# AFE1.net
KiCad netlist of a schematic drawn in Altium Designer
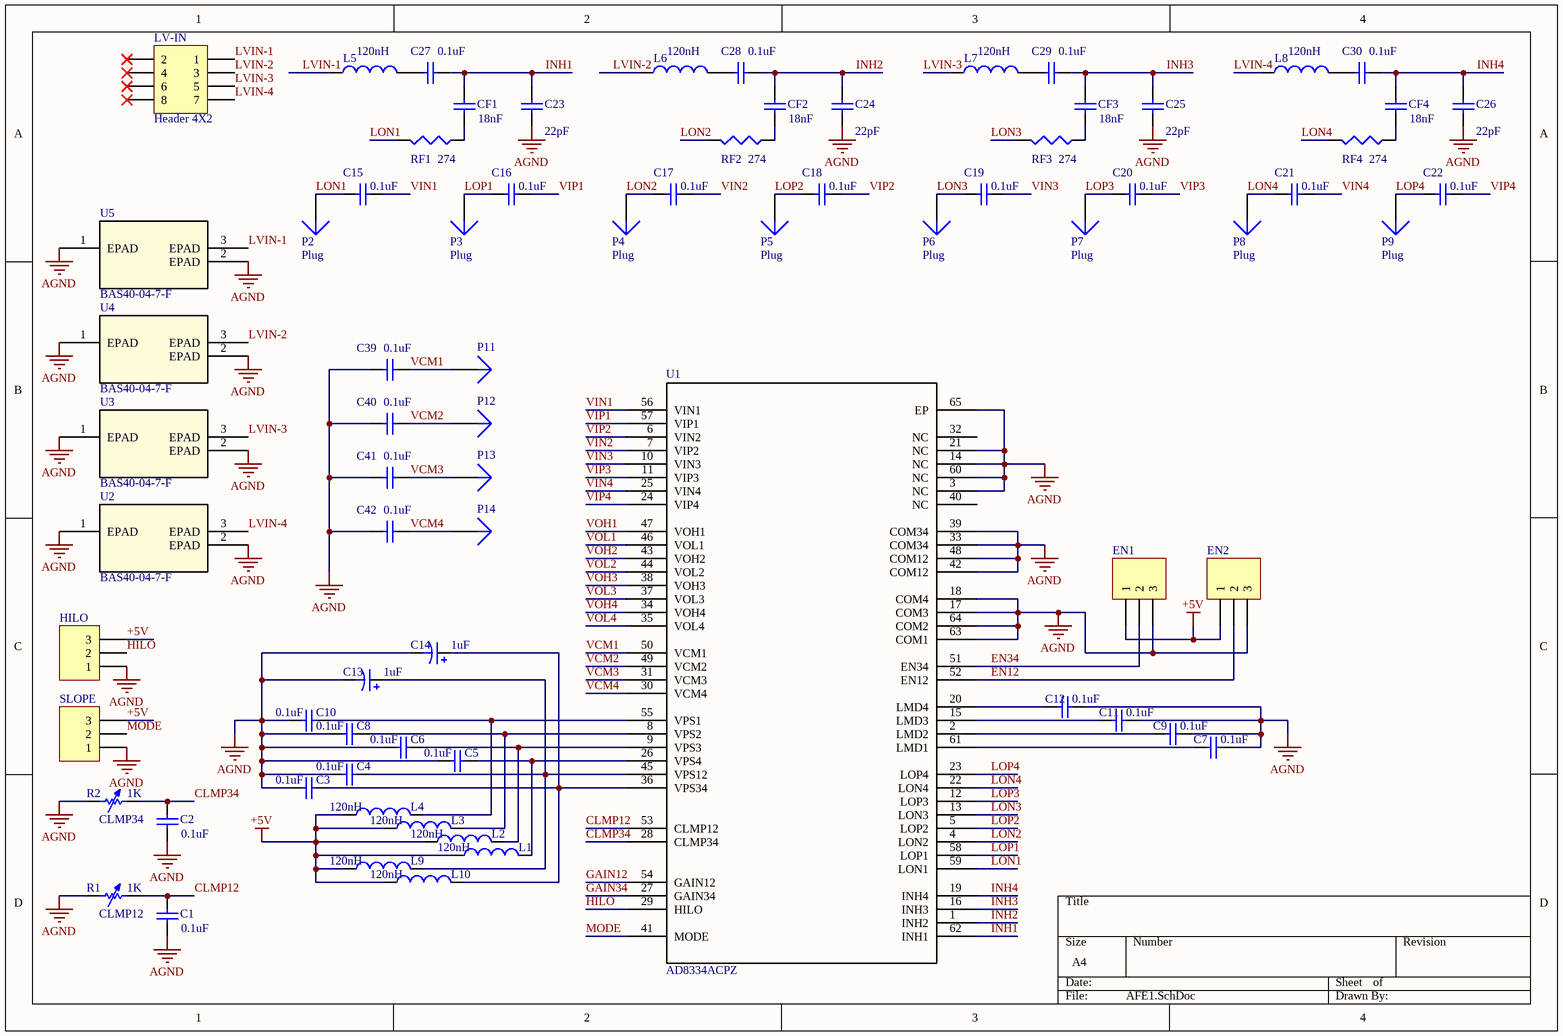
[diagram p0: AFE1.SchDoc]

(export (version "E")
  (design (tool "Eeschema 10.0.6"))
  (components
    (comp (ref "C1")
      (value "0.1uF")
      (footprint "1608[0603]")
      (description "Capacitor (Semiconductor SIM Model)")
      (fields (field (name "PUBLISHER") "Altium Limited"))
      (libsource (lib "Miscellaneous Devices") (part "Cap Semi"))
    )
    (comp (ref "C2")
      (value "0.1uF")
      (footprint "1608[0603]")
      (description "Capacitor (Semiconductor SIM Model)")
      (fields (field (name "PUBLISHER") "Altium Limited"))
      (libsource (lib "Miscellaneous Devices") (part "Cap Semi"))
    )
    (comp (ref "C3")
      (value "0.1uF")
      (footprint "1608[0603]")
      (description "Capacitor (Semiconductor SIM Model)")
      (fields (field (name "PUBLISHER") "Altium Limited"))
      (libsource (lib "Miscellaneous Devices") (part "Cap Semi"))
    )
    (comp (ref "C4")
      (value "0.1uF")
      (footprint "1608[0603]")
      (description "Capacitor (Semiconductor SIM Model)")
      (fields (field (name "PUBLISHER") "Altium Limited"))
      (libsource (lib "Miscellaneous Devices") (part "Cap Semi"))
    )
    (comp (ref "C5")
      (value "0.1uF")
      (footprint "1608[0603]")
      (description "Capacitor (Semiconductor SIM Model)")
      (fields (field (name "PUBLISHER") "Altium Limited"))
      (libsource (lib "Miscellaneous Devices") (part "Cap Semi"))
    )
    (comp (ref "C6")
      (value "0.1uF")
      (footprint "1608[0603]")
      (description "Capacitor (Semiconductor SIM Model)")
      (fields (field (name "PUBLISHER") "Altium Limited"))
      (libsource (lib "Miscellaneous Devices") (part "Cap Semi"))
    )
    (comp (ref "C7")
      (value "0.1uF")
      (footprint "1608[0603]")
      (description "Capacitor (Semiconductor SIM Model)")
      (fields (field (name "PUBLISHER") "Altium Limited"))
      (libsource (lib "Miscellaneous Devices") (part "Cap Semi"))
    )
    (comp (ref "C8")
      (value "0.1uF")
      (footprint "1608[0603]")
      (description "Capacitor (Semiconductor SIM Model)")
      (fields (field (name "PUBLISHER") "Altium Limited"))
      (libsource (lib "Miscellaneous Devices") (part "Cap Semi"))
    )
    (comp (ref "C9")
      (value "0.1uF")
      (footprint "1608[0603]")
      (description "Capacitor (Semiconductor SIM Model)")
      (fields (field (name "PUBLISHER") "Altium Limited"))
      (libsource (lib "Miscellaneous Devices") (part "Cap Semi"))
    )
    (comp (ref "C10")
      (value "0.1uF")
      (footprint "1608[0603]")
      (description "Capacitor (Semiconductor SIM Model)")
      (fields (field (name "PUBLISHER") "Altium Limited"))
      (libsource (lib "Miscellaneous Devices") (part "Cap Semi"))
    )
    (comp (ref "C11")
      (value "0.1uF")
      (footprint "1608[0603]")
      (description "Capacitor (Semiconductor SIM Model)")
      (fields (field (name "PUBLISHER") "Altium Limited"))
      (libsource (lib "Miscellaneous Devices") (part "Cap Semi"))
    )
    (comp (ref "C12")
      (value "0.1uF")
      (footprint "1608[0603]")
      (description "Capacitor (Semiconductor SIM Model)")
      (fields (field (name "PUBLISHER") "Altium Limited"))
      (libsource (lib "Miscellaneous Devices") (part "Cap Semi"))
    )
    (comp (ref "C13")
      (value "1uF")
      (footprint "C0805")
      (description "Polarized Capacitor (Surface Mount)")
      (fields (field (name "PUBLISHER") "Altium Limited"))
      (libsource (lib "Miscellaneous Devices") (part "Cap Pol3"))
    )
    (comp (ref "C14")
      (value "1uF")
      (footprint "C0805")
      (description "Polarized Capacitor (Surface Mount)")
      (fields (field (name "PUBLISHER") "Altium Limited"))
      (libsource (lib "Miscellaneous Devices") (part "Cap Pol3"))
    )
    (comp (ref "C15")
      (value "0.1uF")
      (footprint "1608[0603]")
      (description "Capacitor (Semiconductor SIM Model)")
      (fields (field (name "PUBLISHER") "Altium Limited"))
      (libsource (lib "Miscellaneous Devices") (part "Cap Semi"))
    )
    (comp (ref "C16")
      (value "0.1uF")
      (footprint "1608[0603]")
      (description "Capacitor (Semiconductor SIM Model)")
      (fields (field (name "PUBLISHER") "Altium Limited"))
      (libsource (lib "Miscellaneous Devices") (part "Cap Semi"))
    )
    (comp (ref "C17")
      (value "0.1uF")
      (footprint "1608[0603]")
      (description "Capacitor (Semiconductor SIM Model)")
      (fields (field (name "PUBLISHER") "Altium Limited"))
      (libsource (lib "Miscellaneous Devices") (part "Cap Semi"))
    )
    (comp (ref "C18")
      (value "0.1uF")
      (footprint "1608[0603]")
      (description "Capacitor (Semiconductor SIM Model)")
      (fields (field (name "PUBLISHER") "Altium Limited"))
      (libsource (lib "Miscellaneous Devices") (part "Cap Semi"))
    )
    (comp (ref "C19")
      (value "0.1uF")
      (footprint "1608[0603]")
      (description "Capacitor (Semiconductor SIM Model)")
      (fields (field (name "PUBLISHER") "Altium Limited"))
      (libsource (lib "Miscellaneous Devices") (part "Cap Semi"))
    )
    (comp (ref "C20")
      (value "0.1uF")
      (footprint "1608[0603]")
      (description "Capacitor (Semiconductor SIM Model)")
      (fields (field (name "PUBLISHER") "Altium Limited"))
      (libsource (lib "Miscellaneous Devices") (part "Cap Semi"))
    )
    (comp (ref "C21")
      (value "0.1uF")
      (footprint "1608[0603]")
      (description "Capacitor (Semiconductor SIM Model)")
      (fields (field (name "PUBLISHER") "Altium Limited"))
      (libsource (lib "Miscellaneous Devices") (part "Cap Semi"))
    )
    (comp (ref "C22")
      (value "0.1uF")
      (footprint "1608[0603]")
      (description "Capacitor (Semiconductor SIM Model)")
      (fields (field (name "PUBLISHER") "Altium Limited"))
      (libsource (lib "Miscellaneous Devices") (part "Cap Semi"))
    )
    (comp (ref "C23")
      (value "22pF")
      (footprint "1608[0603]")
      (description "Capacitor (Semiconductor SIM Model)")
      (fields (field (name "PUBLISHER") "Altium Limited"))
      (libsource (lib "Miscellaneous Devices") (part "Cap Semi"))
    )
    (comp (ref "C24")
      (value "22pF")
      (footprint "1608[0603]")
      (description "Capacitor (Semiconductor SIM Model)")
      (fields (field (name "PUBLISHER") "Altium Limited"))
      (libsource (lib "Miscellaneous Devices") (part "Cap Semi"))
    )
    (comp (ref "C25")
      (value "22pF")
      (footprint "1608[0603]")
      (description "Capacitor (Semiconductor SIM Model)")
      (fields (field (name "PUBLISHER") "Altium Limited"))
      (libsource (lib "Miscellaneous Devices") (part "Cap Semi"))
    )
    (comp (ref "C26")
      (value "22pF")
      (footprint "1608[0603]")
      (description "Capacitor (Semiconductor SIM Model)")
      (fields (field (name "PUBLISHER") "Altium Limited"))
      (libsource (lib "Miscellaneous Devices") (part "Cap Semi"))
    )
    (comp (ref "C27")
      (value "0.1uF")
      (footprint "1608[0603]")
      (description "Capacitor (Semiconductor SIM Model)")
      (fields (field (name "PUBLISHER") "Altium Limited"))
      (libsource (lib "Miscellaneous Devices") (part "Cap Semi"))
    )
    (comp (ref "C28")
      (value "0.1uF")
      (footprint "1608[0603]")
      (description "Capacitor (Semiconductor SIM Model)")
      (fields (field (name "PUBLISHER") "Altium Limited"))
      (libsource (lib "Miscellaneous Devices") (part "Cap Semi"))
    )
    (comp (ref "C29")
      (value "0.1uF")
      (footprint "1608[0603]")
      (description "Capacitor (Semiconductor SIM Model)")
      (fields (field (name "PUBLISHER") "Altium Limited"))
      (libsource (lib "Miscellaneous Devices") (part "Cap Semi"))
    )
    (comp (ref "C30")
      (value "0.1uF")
      (footprint "1608[0603]")
      (description "Capacitor (Semiconductor SIM Model)")
      (fields (field (name "PUBLISHER") "Altium Limited"))
      (libsource (lib "Miscellaneous Devices") (part "Cap Semi"))
    )
    (comp (ref "C39")
      (value "0.1uF")
      (footprint "1608[0603]")
      (description "Capacitor (Semiconductor SIM Model)")
      (fields (field (name "PUBLISHER") "Altium Limited"))
      (libsource (lib "Miscellaneous Devices") (part "Cap Semi"))
    )
    (comp (ref "C40")
      (value "0.1uF")
      (footprint "1608[0603]")
      (description "Capacitor (Semiconductor SIM Model)")
      (fields (field (name "PUBLISHER") "Altium Limited"))
      (libsource (lib "Miscellaneous Devices") (part "Cap Semi"))
    )
    (comp (ref "C41")
      (value "0.1uF")
      (footprint "1608[0603]")
      (description "Capacitor (Semiconductor SIM Model)")
      (fields (field (name "PUBLISHER") "Altium Limited"))
      (libsource (lib "Miscellaneous Devices") (part "Cap Semi"))
    )
    (comp (ref "C42")
      (value "0.1uF")
      (footprint "1608[0603]")
      (description "Capacitor (Semiconductor SIM Model)")
      (fields (field (name "PUBLISHER") "Altium Limited"))
      (libsource (lib "Miscellaneous Devices") (part "Cap Semi"))
    )
    (comp (ref "CF1")
      (value "18nF")
      (footprint "1608[0603]")
      (description "Capacitor (Semiconductor SIM Model)")
      (fields (field (name "PUBLISHER") "Altium Limited"))
      (libsource (lib "Miscellaneous Devices") (part "Cap Semi"))
    )
    (comp (ref "CF2")
      (value "18nF")
      (footprint "1608[0603]")
      (description "Capacitor (Semiconductor SIM Model)")
      (fields (field (name "PUBLISHER") "Altium Limited"))
      (libsource (lib "Miscellaneous Devices") (part "Cap Semi"))
    )
    (comp (ref "CF3")
      (value "18nF")
      (footprint "1608[0603]")
      (description "Capacitor (Semiconductor SIM Model)")
      (fields (field (name "PUBLISHER") "Altium Limited"))
      (libsource (lib "Miscellaneous Devices") (part "Cap Semi"))
    )
    (comp (ref "CF4")
      (value "18nF")
      (footprint "1608[0603]")
      (description "Capacitor (Semiconductor SIM Model)")
      (fields (field (name "PUBLISHER") "Altium Limited"))
      (libsource (lib "Miscellaneous Devices") (part "Cap Semi"))
    )
    (comp (ref "EN1")
      (value "~")
      (footprint "HDR1X3")
      (description "Header, 3-Pin")
      (fields (field (name "PUBLISHER") "Altium Limited"))
      (libsource (lib "") (part "Header 3_1"))
    )
    (comp (ref "EN2")
      (value "~")
      (footprint "HDR1X3")
      (description "Header, 3-Pin")
      (fields (field (name "PUBLISHER") "Altium Limited"))
      (libsource (lib "") (part "Header 3_1"))
    )
    (comp (ref "HILO")
      (value "~")
      (footprint "HDR1X3")
      (description "Header, 3-Pin")
      (fields (field (name "PUBLISHER") "Altium Limited"))
      (libsource (lib "Miscellaneous Connectors") (part "Header 3"))
    )
    (comp (ref "L1")
      (value "120nH")
      (footprint "INDC1608L")
      (description "Inductor")
      (fields (field (name "PUBLISHER") "Altium Limited"))
      (libsource (lib "Miscellaneous Devices") (part "Inductor"))
    )
    (comp (ref "L2")
      (value "120nH")
      (footprint "INDC1608L")
      (description "Inductor")
      (fields (field (name "PUBLISHER") "Altium Limited"))
      (libsource (lib "Miscellaneous Devices") (part "Inductor"))
    )
    (comp (ref "L3")
      (value "120nH")
      (footprint "INDC1608L")
      (description "Inductor")
      (fields (field (name "PUBLISHER") "Altium Limited"))
      (libsource (lib "Miscellaneous Devices") (part "Inductor"))
    )
    (comp (ref "L4")
      (value "120nH")
      (footprint "INDC1608L")
      (description "Inductor")
      (fields (field (name "PUBLISHER") "Altium Limited"))
      (libsource (lib "Miscellaneous Devices") (part "Inductor"))
    )
    (comp (ref "L5")
      (value "120nH")
      (footprint "INDC1608L")
      (description "Inductor")
      (fields (field (name "PUBLISHER") "Altium Limited"))
      (libsource (lib "Miscellaneous Devices") (part "Inductor"))
    )
    (comp (ref "L6")
      (value "120nH")
      (footprint "INDC1608L")
      (description "Inductor")
      (fields (field (name "PUBLISHER") "Altium Limited"))
      (libsource (lib "Miscellaneous Devices") (part "Inductor"))
    )
    (comp (ref "L7")
      (value "120nH")
      (footprint "INDC1608L")
      (description "Inductor")
      (fields (field (name "PUBLISHER") "Altium Limited"))
      (libsource (lib "Miscellaneous Devices") (part "Inductor"))
    )
    (comp (ref "L8")
      (value "120nH")
      (footprint "INDC1608L")
      (description "Inductor")
      (fields (field (name "PUBLISHER") "Altium Limited"))
      (libsource (lib "Miscellaneous Devices") (part "Inductor"))
    )
    (comp (ref "L9")
      (value "120nH")
      (footprint "INDC1608L")
      (description "Inductor")
      (fields (field (name "PUBLISHER") "Altium Limited"))
      (libsource (lib "Miscellaneous Devices") (part "Inductor"))
    )
    (comp (ref "L10")
      (value "120nH")
      (footprint "INDC1608L")
      (description "Inductor")
      (fields (field (name "PUBLISHER") "Altium Limited"))
      (libsource (lib "Miscellaneous Devices") (part "Inductor"))
    )
    (comp (ref "LV-IN")
      (value "Header 4X2")
      (footprint "HDR2X4")
      (description "Header, 4-Pin, Dual row")
      (fields (field (name "PUBLISHER") "Altium Limited"))
      (libsource (lib "Miscellaneous Connectors") (part "Header 4X2"))
    )
    (comp (ref "P2")
      (value "Plug")
      (footprint "PIN1")
      (fields (field (name "PUBLISHER") "Altium Limited"))
      (libsource (lib "Miscellaneous Connectors") (part "Plug"))
    )
    (comp (ref "P3")
      (value "Plug")
      (footprint "PIN1")
      (fields (field (name "PUBLISHER") "Altium Limited"))
      (libsource (lib "Miscellaneous Connectors") (part "Plug"))
    )
    (comp (ref "P4")
      (value "Plug")
      (footprint "PIN1")
      (fields (field (name "PUBLISHER") "Altium Limited"))
      (libsource (lib "Miscellaneous Connectors") (part "Plug"))
    )
    (comp (ref "P5")
      (value "Plug")
      (footprint "PIN1")
      (fields (field (name "PUBLISHER") "Altium Limited"))
      (libsource (lib "Miscellaneous Connectors") (part "Plug"))
    )
    (comp (ref "P6")
      (value "Plug")
      (footprint "PIN1")
      (fields (field (name "PUBLISHER") "Altium Limited"))
      (libsource (lib "Miscellaneous Connectors") (part "Plug"))
    )
    (comp (ref "P7")
      (value "Plug")
      (footprint "PIN1")
      (fields (field (name "PUBLISHER") "Altium Limited"))
      (libsource (lib "Miscellaneous Connectors") (part "Plug"))
    )
    (comp (ref "P8")
      (value "Plug")
      (footprint "PIN1")
      (fields (field (name "PUBLISHER") "Altium Limited"))
      (libsource (lib "Miscellaneous Connectors") (part "Plug"))
    )
    (comp (ref "P9")
      (value "Plug")
      (footprint "PIN1")
      (fields (field (name "PUBLISHER") "Altium Limited"))
      (libsource (lib "Miscellaneous Connectors") (part "Plug"))
    )
    (comp (ref "P11")
      (value "~")
      (footprint "PIN1")
      (description "Plug")
      (fields (field (name "PUBLISHER") "Altium Limited"))
      (libsource (lib "Miscellaneous Connectors") (part "Plug"))
    )
    (comp (ref "P12")
      (value "~")
      (footprint "PIN1")
      (description "Plug")
      (fields (field (name "PUBLISHER") "Altium Limited"))
      (libsource (lib "Miscellaneous Connectors") (part "Plug"))
    )
    (comp (ref "P13")
      (value "~")
      (footprint "PIN1")
      (description "Plug")
      (fields (field (name "PUBLISHER") "Altium Limited"))
      (libsource (lib "Miscellaneous Connectors") (part "Plug"))
    )
    (comp (ref "P14")
      (value "~")
      (footprint "PIN1")
      (description "Plug")
      (fields (field (name "PUBLISHER") "Altium Limited"))
      (libsource (lib "Miscellaneous Connectors") (part "Plug"))
    )
    (comp (ref "R1")
      (value "CLMP12")
      (footprint "Miscellaneous Devices:SMB")
      (description "Variable Resistor")
      (fields (field (name "ALTIUM_VALUE") "1K") (field (name "PUBLISHER") "Altium Limited"))
      (libsource (lib "Miscellaneous Devices") (part "Res Adj1"))
    )
    (comp (ref "R2")
      (value "CLMP34")
      (footprint "Miscellaneous Devices:SMB")
      (description "Variable Resistor")
      (fields (field (name "ALTIUM_VALUE") "1K") (field (name "PUBLISHER") "Altium Limited"))
      (libsource (lib "Miscellaneous Devices") (part "Res Adj1"))
    )
    (comp (ref "RF1")
      (value "274")
      (footprint "J1-0603")
      (description "Resistor")
      (fields (field (name "PUBLISHER") "Altium Limited"))
      (libsource (lib "Miscellaneous Devices") (part "Res3"))
    )
    (comp (ref "RF2")
      (value "274")
      (footprint "J1-0603")
      (description "Resistor")
      (fields (field (name "PUBLISHER") "Altium Limited"))
      (libsource (lib "Miscellaneous Devices") (part "Res3"))
    )
    (comp (ref "RF3")
      (value "274")
      (footprint "J1-0603")
      (description "Resistor")
      (fields (field (name "PUBLISHER") "Altium Limited"))
      (libsource (lib "Miscellaneous Devices") (part "Res3"))
    )
    (comp (ref "RF4")
      (value "274")
      (footprint "J1-0603")
      (description "Resistor")
      (fields (field (name "PUBLISHER") "Altium Limited"))
      (libsource (lib "Miscellaneous Devices") (part "Res3"))
    )
    (comp (ref "SLOPE")
      (value "~")
      (footprint "HDR1X3")
      (description "Header, 3-Pin")
      (fields (field (name "PUBLISHER") "Altium Limited"))
      (libsource (lib "Miscellaneous Connectors") (part "Header 3"))
    )
    (comp (ref "U1")
      (value "AD8334ACPZ")
      (footprint "CP_64_1")
      (description "Imported")
      (libsource (lib "AD8334ACPZ") (part "AD8334ACPZ"))
    )
    (comp (ref "U2")
      (value "BAS40-04-7-F")
      (footprint "SOT-23")
      (description "Imported")
      (libsource (lib "BAS40-04") (part "BAS40-04-7-F"))
    )
    (comp (ref "U3")
      (value "BAS40-04-7-F")
      (footprint "SOT-23")
      (description "Imported")
      (libsource (lib "BAS40-04") (part "BAS40-04-7-F"))
    )
    (comp (ref "U4")
      (value "BAS40-04-7-F")
      (footprint "SOT-23")
      (description "Imported")
      (libsource (lib "BAS40-04") (part "BAS40-04-7-F"))
    )
    (comp (ref "U5")
      (value "BAS40-04-7-F")
      (footprint "SOT-23")
      (description "Imported")
      (libsource (lib "BAS40-04") (part "BAS40-04-7-F"))
    )
  )
  (nets
    (net (code "1") (name "+5V") (class "Default")
      (node (ref "EN1") (pin "1") (pinfunction "1_1") (pintype "passive"))
      (node (ref "EN2") (pin "1") (pinfunction "1_1") (pintype "passive"))
      (node (ref "HILO") (pin "3") (pinfunction "3_3") (pintype "passive"))
      (node (ref "L1") (pin "1") (pinfunction "1_1") (pintype "passive"))
      (node (ref "L10") (pin "1") (pinfunction "1_1") (pintype "passive"))
      (node (ref "L2") (pin "1") (pinfunction "1_1") (pintype "passive"))
      (node (ref "L3") (pin "1") (pinfunction "1_1") (pintype "passive"))
      (node (ref "L4") (pin "1") (pinfunction "1_1") (pintype "passive"))
      (node (ref "L9") (pin "1") (pinfunction "1_1") (pintype "passive"))
      (node (ref "SLOPE") (pin "3") (pinfunction "3_3") (pintype "passive"))
    )
    (net (code "2") (name "/CLMP12") (class "Default")
      (node (ref "C1") (pin "2") (pinfunction "2_2") (pintype "passive"))
      (node (ref "R1") (pin "2") (pinfunction "2_2") (pintype "passive"))
      (node (ref "U1") (pin "53") (pinfunction "CLMP12_53") (pintype "passive"))
    )
    (net (code "3") (name "/CLMP34") (class "Default")
      (node (ref "C2") (pin "2") (pinfunction "2_2") (pintype "passive"))
      (node (ref "R2") (pin "2") (pinfunction "2_2") (pintype "passive"))
      (node (ref "U1") (pin "28") (pinfunction "CLMP34_28") (pintype "passive"))
    )
    (net (code "4") (name "/EN12") (class "Default")
      (node (ref "EN2") (pin "2") (pinfunction "2_2") (pintype "passive"))
      (node (ref "U1") (pin "52") (pinfunction "EN12_52") (pintype "passive"))
    )
    (net (code "5") (name "/EN34") (class "Default")
      (node (ref "EN1") (pin "2") (pinfunction "2_2") (pintype "passive"))
      (node (ref "U1") (pin "51") (pinfunction "EN34_51") (pintype "passive"))
    )
    (net (code "6") (name "/GAIN12") (class "Default")
      (node (ref "U1") (pin "54") (pinfunction "GAIN12_54") (pintype "passive"))
    )
    (net (code "7") (name "/GAIN34") (class "Default")
      (node (ref "U1") (pin "27") (pinfunction "GAIN34_27") (pintype "passive"))
    )
    (net (code "8") (name "/HILO") (class "Default")
      (node (ref "HILO") (pin "2") (pinfunction "2_2") (pintype "passive"))
      (node (ref "U1") (pin "29") (pinfunction "HILO_29") (pintype "passive"))
    )
    (net (code "9") (name "/INH1") (class "Default")
      (node (ref "C23") (pin "2") (pinfunction "2_2") (pintype "passive"))
      (node (ref "C27") (pin "2") (pinfunction "2_2") (pintype "passive"))
      (node (ref "CF1") (pin "2") (pinfunction "2_2") (pintype "passive"))
      (node (ref "U1") (pin "62") (pinfunction "INH1_62") (pintype "passive"))
    )
    (net (code "10") (name "/INH2") (class "Default")
      (node (ref "C24") (pin "2") (pinfunction "2_2") (pintype "passive"))
      (node (ref "C28") (pin "2") (pinfunction "2_2") (pintype "passive"))
      (node (ref "CF2") (pin "2") (pinfunction "2_2") (pintype "passive"))
      (node (ref "U1") (pin "1") (pinfunction "INH2_1") (pintype "passive"))
    )
    (net (code "11") (name "/INH3") (class "Default")
      (node (ref "C25") (pin "2") (pinfunction "2_2") (pintype "passive"))
      (node (ref "C29") (pin "2") (pinfunction "2_2") (pintype "passive"))
      (node (ref "CF3") (pin "2") (pinfunction "2_2") (pintype "passive"))
      (node (ref "U1") (pin "16") (pinfunction "INH3_16") (pintype "passive"))
    )
    (net (code "12") (name "/INH4") (class "Default")
      (node (ref "C26") (pin "2") (pinfunction "2_2") (pintype "passive"))
      (node (ref "C30") (pin "2") (pinfunction "2_2") (pintype "passive"))
      (node (ref "CF4") (pin "2") (pinfunction "2_2") (pintype "passive"))
      (node (ref "U1") (pin "19") (pinfunction "INH4_19") (pintype "passive"))
    )
    (net (code "13") (name "/LON1") (class "Default")
      (node (ref "C15") (pin "1") (pinfunction "1_1") (pintype "passive"))
      (node (ref "P2") (pin "1") (pinfunction "1_1") (pintype "passive"))
      (node (ref "RF1") (pin "2") (pinfunction "2_2") (pintype "passive"))
      (node (ref "U1") (pin "59") (pinfunction "LON1_59") (pintype "passive"))
    )
    (net (code "14") (name "/LON2") (class "Default")
      (node (ref "C17") (pin "1") (pinfunction "1_1") (pintype "passive"))
      (node (ref "P4") (pin "1") (pinfunction "1_1") (pintype "passive"))
      (node (ref "RF2") (pin "2") (pinfunction "2_2") (pintype "passive"))
      (node (ref "U1") (pin "4") (pinfunction "LON2_4") (pintype "passive"))
    )
    (net (code "15") (name "/LON3") (class "Default")
      (node (ref "C19") (pin "1") (pinfunction "1_1") (pintype "passive"))
      (node (ref "P6") (pin "1") (pinfunction "1_1") (pintype "passive"))
      (node (ref "RF3") (pin "2") (pinfunction "2_2") (pintype "passive"))
      (node (ref "U1") (pin "13") (pinfunction "LON3_13") (pintype "passive"))
    )
    (net (code "16") (name "/LON4") (class "Default")
      (node (ref "C21") (pin "1") (pinfunction "1_1") (pintype "passive"))
      (node (ref "P8") (pin "1") (pinfunction "1_1") (pintype "passive"))
      (node (ref "RF4") (pin "2") (pinfunction "2_2") (pintype "passive"))
      (node (ref "U1") (pin "22") (pinfunction "LON4_22") (pintype "passive"))
    )
    (net (code "17") (name "/LOP1") (class "Default")
      (node (ref "C16") (pin "1") (pinfunction "1_1") (pintype "passive"))
      (node (ref "P3") (pin "1") (pinfunction "1_1") (pintype "passive"))
      (node (ref "U1") (pin "58") (pinfunction "LOP1_58") (pintype "passive"))
    )
    (net (code "18") (name "/LOP2") (class "Default")
      (node (ref "C18") (pin "1") (pinfunction "1_1") (pintype "passive"))
      (node (ref "P5") (pin "1") (pinfunction "1_1") (pintype "passive"))
      (node (ref "U1") (pin "5") (pinfunction "LOP2_5") (pintype "passive"))
    )
    (net (code "19") (name "/LOP3") (class "Default")
      (node (ref "C20") (pin "1") (pinfunction "1_1") (pintype "passive"))
      (node (ref "P7") (pin "1") (pinfunction "1_1") (pintype "passive"))
      (node (ref "U1") (pin "12") (pinfunction "LOP3_12") (pintype "passive"))
    )
    (net (code "20") (name "/LOP4") (class "Default")
      (node (ref "C22") (pin "1") (pinfunction "1_1") (pintype "passive"))
      (node (ref "P9") (pin "1") (pinfunction "1_1") (pintype "passive"))
      (node (ref "U1") (pin "23") (pinfunction "LOP4_23") (pintype "passive"))
    )
    (net (code "21") (name "/LVIN-1") (class "Default")
      (node (ref "L5") (pin "1") (pinfunction "1_1") (pintype "passive"))
      (node (ref "LV-IN") (pin "1") (pinfunction "1_1") (pintype "passive"))
      (node (ref "U5") (pin "3") (pinfunction "EPAD_3") (pintype "passive"))
    )
    (net (code "22") (name "/LVIN-2") (class "Default")
      (node (ref "L6") (pin "1") (pinfunction "1_1") (pintype "passive"))
      (node (ref "LV-IN") (pin "3") (pinfunction "3_3") (pintype "passive"))
      (node (ref "U4") (pin "3") (pinfunction "EPAD_3") (pintype "passive"))
    )
    (net (code "23") (name "/LVIN-3") (class "Default")
      (node (ref "L7") (pin "1") (pinfunction "1_1") (pintype "passive"))
      (node (ref "LV-IN") (pin "5") (pinfunction "5_5") (pintype "passive"))
      (node (ref "U3") (pin "3") (pinfunction "EPAD_3") (pintype "passive"))
    )
    (net (code "24") (name "/LVIN-4") (class "Default")
      (node (ref "L8") (pin "1") (pinfunction "1_1") (pintype "passive"))
      (node (ref "LV-IN") (pin "7") (pinfunction "7_7") (pintype "passive"))
      (node (ref "U2") (pin "3") (pinfunction "EPAD_3") (pintype "passive"))
    )
    (net (code "25") (name "/MODE") (class "Default")
      (node (ref "SLOPE") (pin "2") (pinfunction "2_2") (pintype "passive"))
      (node (ref "U1") (pin "41") (pinfunction "MODE_41") (pintype "passive"))
    )
    (net (code "26") (name "/VCM1") (class "Default")
      (node (ref "C39") (pin "1") (pinfunction "1_1") (pintype "passive"))
      (node (ref "P11") (pin "1") (pinfunction "1_1") (pintype "passive"))
      (node (ref "U1") (pin "50") (pinfunction "VCM1_50") (pintype "passive"))
    )
    (net (code "27") (name "/VCM2") (class "Default")
      (node (ref "C40") (pin "1") (pinfunction "1_1") (pintype "passive"))
      (node (ref "P12") (pin "1") (pinfunction "1_1") (pintype "passive"))
      (node (ref "U1") (pin "49") (pinfunction "VCM2_49") (pintype "passive"))
    )
    (net (code "28") (name "/VCM3") (class "Default")
      (node (ref "C41") (pin "1") (pinfunction "1_1") (pintype "passive"))
      (node (ref "P13") (pin "1") (pinfunction "1_1") (pintype "passive"))
      (node (ref "U1") (pin "31") (pinfunction "VCM3_31") (pintype "passive"))
    )
    (net (code "29") (name "/VCM4") (class "Default")
      (node (ref "C42") (pin "1") (pinfunction "1_1") (pintype "passive"))
      (node (ref "P14") (pin "1") (pinfunction "1_1") (pintype "passive"))
      (node (ref "U1") (pin "30") (pinfunction "VCM4_30") (pintype "passive"))
    )
    (net (code "30") (name "/VIN1") (class "Default")
      (node (ref "C15") (pin "2") (pinfunction "2_2") (pintype "passive"))
      (node (ref "U1") (pin "56") (pinfunction "VIN1_56") (pintype "passive"))
    )
    (net (code "31") (name "/VIN2") (class "Default")
      (node (ref "C17") (pin "2") (pinfunction "2_2") (pintype "passive"))
      (node (ref "U1") (pin "7") (pinfunction "VIP2_7") (pintype "passive"))
    )
    (net (code "32") (name "/VIN3") (class "Default")
      (node (ref "C19") (pin "2") (pinfunction "2_2") (pintype "passive"))
      (node (ref "U1") (pin "10") (pinfunction "VIN3_10") (pintype "passive"))
    )
    (net (code "33") (name "/VIN4") (class "Default")
      (node (ref "C21") (pin "2") (pinfunction "2_2") (pintype "passive"))
      (node (ref "U1") (pin "25") (pinfunction "VIN4_25") (pintype "passive"))
    )
    (net (code "34") (name "/VIP1") (class "Default")
      (node (ref "C16") (pin "2") (pinfunction "2_2") (pintype "passive"))
      (node (ref "U1") (pin "57") (pinfunction "VIP1_57") (pintype "passive"))
    )
    (net (code "35") (name "/VIP2") (class "Default")
      (node (ref "C18") (pin "2") (pinfunction "2_2") (pintype "passive"))
      (node (ref "U1") (pin "6") (pinfunction "VIN2_6") (pintype "passive"))
    )
    (net (code "36") (name "/VIP3") (class "Default")
      (node (ref "C20") (pin "2") (pinfunction "2_2") (pintype "passive"))
      (node (ref "U1") (pin "11") (pinfunction "VIP3_11") (pintype "passive"))
    )
    (net (code "37") (name "/VIP4") (class "Default")
      (node (ref "C22") (pin "2") (pinfunction "2_2") (pintype "passive"))
      (node (ref "U1") (pin "24") (pinfunction "VIP4_24") (pintype "passive"))
    )
    (net (code "38") (name "/VOH1") (class "Default")
      (node (ref "U1") (pin "47") (pinfunction "VOH1_47") (pintype "passive"))
    )
    (net (code "39") (name "/VOH2") (class "Default")
      (node (ref "U1") (pin "43") (pinfunction "VOH2_43") (pintype "passive"))
    )
    (net (code "40") (name "/VOH3") (class "Default")
      (node (ref "U1") (pin "38") (pinfunction "VOH3_38") (pintype "passive"))
    )
    (net (code "41") (name "/VOH4") (class "Default")
      (node (ref "U1") (pin "34") (pinfunction "VOH4_34") (pintype "passive"))
    )
    (net (code "42") (name "/VOL1") (class "Default")
      (node (ref "U1") (pin "46") (pinfunction "VOL1_46") (pintype "passive"))
    )
    (net (code "43") (name "/VOL2") (class "Default")
      (node (ref "U1") (pin "44") (pinfunction "VOL2_44") (pintype "passive"))
    )
    (net (code "44") (name "/VOL3") (class "Default")
      (node (ref "U1") (pin "37") (pinfunction "VOL3_37") (pintype "passive"))
    )
    (net (code "45") (name "/VOL4") (class "Default")
      (node (ref "U1") (pin "35") (pinfunction "VOL4_35") (pintype "passive"))
    )
    (net (code "46") (name "AGND") (class "Default")
      (node (ref "C1") (pin "1") (pinfunction "1_1") (pintype "passive"))
      (node (ref "C10") (pin "1") (pinfunction "1_1") (pintype "passive"))
      (node (ref "C11") (pin "1") (pinfunction "1_1") (pintype "passive"))
      (node (ref "C12") (pin "1") (pinfunction "1_1") (pintype "passive"))
      (node (ref "C13") (pin "2") (pinfunction "2_2") (pintype "passive"))
      (node (ref "C14") (pin "2") (pinfunction "2_2") (pintype "passive"))
      (node (ref "C2") (pin "1") (pinfunction "1_1") (pintype "passive"))
      (node (ref "C23") (pin "1") (pinfunction "1_1") (pintype "passive"))
      (node (ref "C24") (pin "1") (pinfunction "1_1") (pintype "passive"))
      (node (ref "C25") (pin "1") (pinfunction "1_1") (pintype "passive"))
      (node (ref "C26") (pin "1") (pinfunction "1_1") (pintype "passive"))
      (node (ref "C3") (pin "1") (pinfunction "1_1") (pintype "passive"))
      (node (ref "C39") (pin "2") (pinfunction "2_2") (pintype "passive"))
      (node (ref "C4") (pin "1") (pinfunction "1_1") (pintype "passive"))
      (node (ref "C40") (pin "2") (pinfunction "2_2") (pintype "passive"))
      (node (ref "C41") (pin "2") (pinfunction "2_2") (pintype "passive"))
      (node (ref "C42") (pin "2") (pinfunction "2_2") (pintype "passive"))
      (node (ref "C5") (pin "1") (pinfunction "1_1") (pintype "passive"))
      (node (ref "C6") (pin "1") (pinfunction "1_1") (pintype "passive"))
      (node (ref "C7") (pin "1") (pinfunction "1_1") (pintype "passive"))
      (node (ref "C8") (pin "1") (pinfunction "1_1") (pintype "passive"))
      (node (ref "C9") (pin "1") (pinfunction "1_1") (pintype "passive"))
      (node (ref "EN1") (pin "3") (pinfunction "3_3") (pintype "passive"))
      (node (ref "EN2") (pin "3") (pinfunction "3_3") (pintype "passive"))
      (node (ref "HILO") (pin "1") (pinfunction "1_1") (pintype "passive"))
      (node (ref "R1") (pin "1") (pinfunction "1_1") (pintype "passive"))
      (node (ref "R2") (pin "1") (pinfunction "1_1") (pintype "passive"))
      (node (ref "SLOPE") (pin "1") (pinfunction "1_1") (pintype "passive"))
      (node (ref "U1") (pin "14") (pinfunction "NC_14") (pintype "passive"))
      (node (ref "U1") (pin "17") (pinfunction "COM3_17") (pintype "passive"))
      (node (ref "U1") (pin "18") (pinfunction "COM4_18") (pintype "passive"))
      (node (ref "U1") (pin "21") (pinfunction "NC_21") (pintype "passive"))
      (node (ref "U1") (pin "3") (pinfunction "NC_3") (pintype "passive"))
      (node (ref "U1") (pin "33") (pinfunction "COM34_33") (pintype "passive"))
      (node (ref "U1") (pin "39") (pinfunction "COM34_39") (pintype "passive"))
      (node (ref "U1") (pin "42") (pinfunction "COM12_42") (pintype "passive"))
      (node (ref "U1") (pin "48") (pinfunction "COM12_48") (pintype "passive"))
      (node (ref "U1") (pin "60") (pinfunction "NC_60") (pintype "passive"))
      (node (ref "U1") (pin "63") (pinfunction "COM1_63") (pintype "passive"))
      (node (ref "U1") (pin "64") (pinfunction "COM2_64") (pintype "passive"))
      (node (ref "U1") (pin "65") (pinfunction "EP_65") (pintype "passive"))
      (node (ref "U2") (pin "1") (pinfunction "EPAD_1") (pintype "passive"))
      (node (ref "U2") (pin "2") (pinfunction "EPAD_2") (pintype "passive"))
      (node (ref "U3") (pin "1") (pinfunction "EPAD_1") (pintype "passive"))
      (node (ref "U3") (pin "2") (pinfunction "EPAD_2") (pintype "passive"))
      (node (ref "U4") (pin "1") (pinfunction "EPAD_1") (pintype "passive"))
      (node (ref "U4") (pin "2") (pinfunction "EPAD_2") (pintype "passive"))
      (node (ref "U5") (pin "1") (pinfunction "EPAD_1") (pintype "passive"))
      (node (ref "U5") (pin "2") (pinfunction "EPAD_2") (pintype "passive"))
    )
    (net (code "47") (name "Net-(C27-Pad1)") (class "Default")
      (node (ref "C27") (pin "1") (pinfunction "1_1") (pintype "passive"))
      (node (ref "L5") (pin "2") (pinfunction "2_2") (pintype "passive"))
    )
    (net (code "48") (name "Net-(C28-Pad1)") (class "Default")
      (node (ref "C28") (pin "1") (pinfunction "1_1") (pintype "passive"))
      (node (ref "L6") (pin "2") (pinfunction "2_2") (pintype "passive"))
    )
    (net (code "49") (name "Net-(C29-Pad1)") (class "Default")
      (node (ref "C29") (pin "1") (pinfunction "1_1") (pintype "passive"))
      (node (ref "L7") (pin "2") (pinfunction "2_2") (pintype "passive"))
    )
    (net (code "50") (name "Net-(C30-Pad1)") (class "Default")
      (node (ref "C30") (pin "1") (pinfunction "1_1") (pintype "passive"))
      (node (ref "L8") (pin "2") (pinfunction "2_2") (pintype "passive"))
    )
    (net (code "51") (name "Net-(CF1-Pad1)") (class "Default")
      (node (ref "CF1") (pin "1") (pinfunction "1_1") (pintype "passive"))
      (node (ref "RF1") (pin "1") (pinfunction "1_1") (pintype "passive"))
    )
    (net (code "52") (name "Net-(CF2-Pad1)") (class "Default")
      (node (ref "CF2") (pin "1") (pinfunction "1_1") (pintype "passive"))
      (node (ref "RF2") (pin "1") (pinfunction "1_1") (pintype "passive"))
    )
    (net (code "53") (name "Net-(CF3-Pad1)") (class "Default")
      (node (ref "CF3") (pin "1") (pinfunction "1_1") (pintype "passive"))
      (node (ref "RF3") (pin "1") (pinfunction "1_1") (pintype "passive"))
    )
    (net (code "54") (name "Net-(CF4-Pad1)") (class "Default")
      (node (ref "CF4") (pin "1") (pinfunction "1_1") (pintype "passive"))
      (node (ref "RF4") (pin "1") (pinfunction "1_1") (pintype "passive"))
    )
    (net (code "55") (name "Net-(U1-LMD1)") (class "Default")
      (node (ref "C7") (pin "2") (pinfunction "2_2") (pintype "passive"))
      (node (ref "U1") (pin "61") (pinfunction "LMD1_61") (pintype "passive"))
    )
    (net (code "56") (name "Net-(U1-LMD2)") (class "Default")
      (node (ref "C9") (pin "2") (pinfunction "2_2") (pintype "passive"))
      (node (ref "U1") (pin "2") (pinfunction "LMD2_2") (pintype "passive"))
    )
    (net (code "57") (name "Net-(U1-LMD3)") (class "Default")
      (node (ref "C11") (pin "2") (pinfunction "2_2") (pintype "passive"))
      (node (ref "U1") (pin "15") (pinfunction "LMD3_15") (pintype "passive"))
    )
    (net (code "58") (name "Net-(U1-LMD4)") (class "Default")
      (node (ref "C12") (pin "2") (pinfunction "2_2") (pintype "passive"))
      (node (ref "U1") (pin "20") (pinfunction "LMD4_20") (pintype "passive"))
    )
    (net (code "59") (name "Net-(U1-VPS1)") (class "Default")
      (node (ref "C10") (pin "2") (pinfunction "2_2") (pintype "passive"))
      (node (ref "L4") (pin "2") (pinfunction "2_2") (pintype "passive"))
      (node (ref "U1") (pin "55") (pinfunction "VPS1_55") (pintype "passive"))
    )
    (net (code "60") (name "Net-(U1-VPS2)") (class "Default")
      (node (ref "C8") (pin "2") (pinfunction "2_2") (pintype "passive"))
      (node (ref "L3") (pin "2") (pinfunction "2_2") (pintype "passive"))
      (node (ref "U1") (pin "8") (pinfunction "VPS2_8") (pintype "passive"))
    )
    (net (code "61") (name "Net-(U1-VPS3)") (class "Default")
      (node (ref "C6") (pin "2") (pinfunction "2_2") (pintype "passive"))
      (node (ref "L2") (pin "2") (pinfunction "2_2") (pintype "passive"))
      (node (ref "U1") (pin "9") (pinfunction "VPS3_9") (pintype "passive"))
    )
    (net (code "62") (name "Net-(U1-VPS4)") (class "Default")
      (node (ref "C5") (pin "2") (pinfunction "2_2") (pintype "passive"))
      (node (ref "L1") (pin "2") (pinfunction "2_2") (pintype "passive"))
      (node (ref "U1") (pin "26") (pinfunction "VPS4_26") (pintype "passive"))
    )
    (net (code "63") (name "Net-(U1-VPS12)") (class "Default")
      (node (ref "C13") (pin "1") (pinfunction "1_1") (pintype "passive"))
      (node (ref "C4") (pin "2") (pinfunction "2_2") (pintype "passive"))
      (node (ref "L9") (pin "2") (pinfunction "2_2") (pintype "passive"))
      (node (ref "U1") (pin "45") (pinfunction "VPS12_45") (pintype "passive"))
    )
    (net (code "64") (name "Net-(U1-VPS34)") (class "Default")
      (node (ref "C14") (pin "1") (pinfunction "1_1") (pintype "passive"))
      (node (ref "C3") (pin "2") (pinfunction "2_2") (pintype "passive"))
      (node (ref "L10") (pin "2") (pinfunction "2_2") (pintype "passive"))
      (node (ref "U1") (pin "36") (pinfunction "VPS34_36") (pintype "passive"))
    )
    (net (code "65") (name "unconnected-(LV-IN-Pad2)") (class "Default")
      (node (ref "LV-IN") (pin "2") (pinfunction "2_2") (pintype "passive+no_connect"))
    )
    (net (code "66") (name "unconnected-(LV-IN-Pad4)") (class "Default")
      (node (ref "LV-IN") (pin "4") (pinfunction "4_4") (pintype "passive+no_connect"))
    )
    (net (code "67") (name "unconnected-(LV-IN-Pad6)") (class "Default")
      (node (ref "LV-IN") (pin "6") (pinfunction "6_6") (pintype "passive+no_connect"))
    )
    (net (code "68") (name "unconnected-(LV-IN-Pad8)") (class "Default")
      (node (ref "LV-IN") (pin "8") (pinfunction "8_8") (pintype "passive+no_connect"))
    )
    (net (code "69") (name "unconnected-(U1-NC-Pad32)") (class "Default")
      (node (ref "U1") (pin "32") (pinfunction "NC_32") (pintype "passive"))
    )
    (net (code "70") (name "unconnected-(U1-NC-Pad40)") (class "Default")
      (node (ref "U1") (pin "40") (pinfunction "NC_40") (pintype "passive"))
    )
  )
)
